# Sheet1.net
KiCad netlist of a schematic drawn in Altium Designer
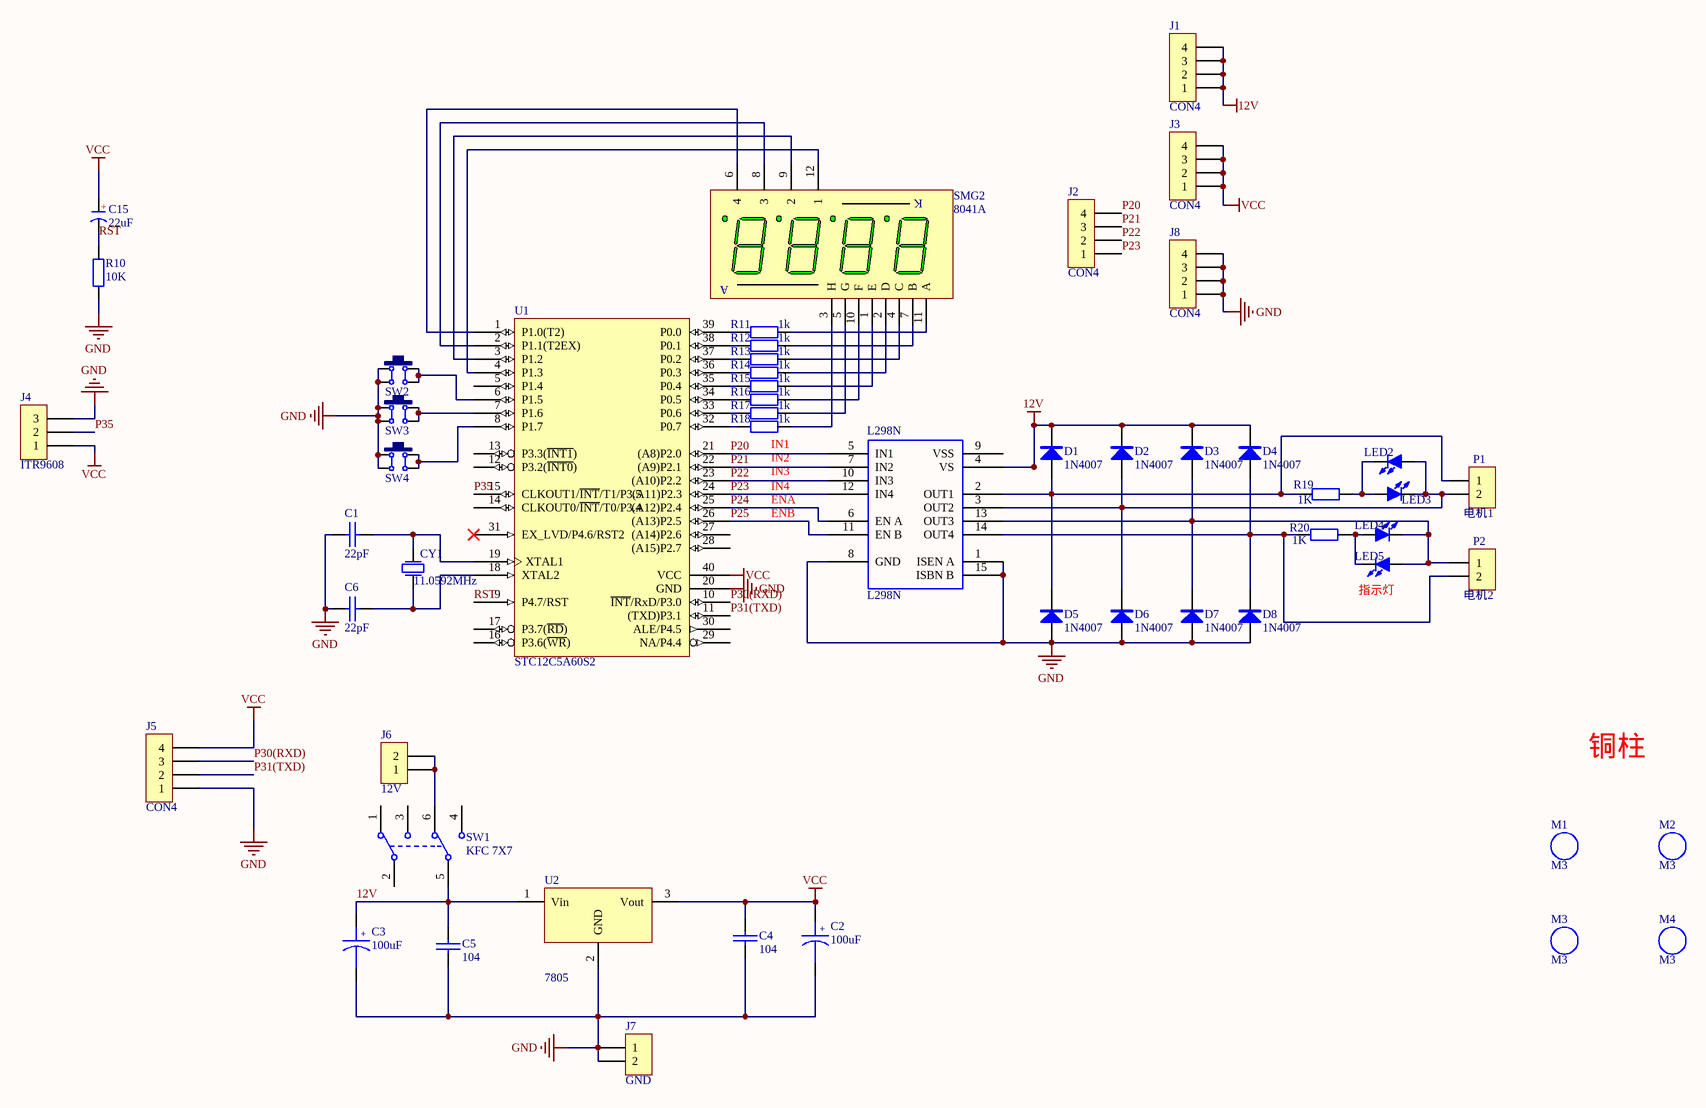
[diagram p0: Sheet1.SchDoc]

(export (version "E")
  (design (tool "Eeschema 10.0.6"))
  (components
    (comp (ref "C1") (value "22pF") (footprint "瓷片电容") (libsource (lib "C电容") (part "CAP1")))
    (comp (ref "C2")
      (value "100uF")
      (footprint "CAP 2.5*5*11")
      (description "Capacitor")
      (libsource (lib "电容") (part "电解电容"))
    )
    (comp (ref "C3")
      (value "100uF")
      (footprint "CAP 2.5*5*11")
      (description "Capacitor")
      (libsource (lib "电容") (part "电解电容"))
    )
    (comp (ref "C4")
      (value "104")
      (footprint "C 0805_M")
      (description "Capacitor")
      (libsource (lib "电容") (part "普通电容"))
    )
    (comp (ref "C5")
      (value "104")
      (footprint "C 0805_M")
      (description "Capacitor")
      (libsource (lib "电容") (part "普通电容"))
    )
    (comp (ref "C6") (value "22pF") (footprint "瓷片电容") (libsource (lib "C电容") (part "CAP1")))
    (comp (ref "C15")
      (value "22uF")
      (footprint "CAP 2.5*5*11")
      (description "直插固态电容")
      (fields (field (name "版权归属") "源创客"))
      (libsource (lib "3.1   - 电阻-电容-电感") (part "C-CS"))
    )
    (comp (ref "CY1") (value "11.0592MHz") (footprint "XTAL-1") (libsource (lib "CRY晶振") (part "CRY")))
    (comp (ref "D1")
      (value "1N4007")
      (footprint "SOD-123")
      (description "整流二极管")
      (fields (field (name "版权归属") "源创客"))
      (libsource (lib "8.1   - 二极管-整流桥") (part "1N4007"))
    )
    (comp (ref "D2")
      (value "1N4007")
      (footprint "SOD-123")
      (description "整流二极管")
      (fields (field (name "版权归属") "源创客"))
      (libsource (lib "8.1   - 二极管-整流桥") (part "1N4007"))
    )
    (comp (ref "D3")
      (value "1N4007")
      (footprint "SOD-123")
      (description "整流二极管")
      (fields (field (name "版权归属") "源创客"))
      (libsource (lib "8.1   - 二极管-整流桥") (part "1N4007"))
    )
    (comp (ref "D4")
      (value "1N4007")
      (footprint "SOD-123")
      (description "整流二极管")
      (fields (field (name "版权归属") "源创客"))
      (libsource (lib "8.1   - 二极管-整流桥") (part "1N4007"))
    )
    (comp (ref "D5")
      (value "1N4007")
      (footprint "SOD-123")
      (description "整流二极管")
      (fields (field (name "版权归属") "源创客"))
      (libsource (lib "8.1   - 二极管-整流桥") (part "1N4007"))
    )
    (comp (ref "D6")
      (value "1N4007")
      (footprint "SOD-123")
      (description "整流二极管")
      (fields (field (name "版权归属") "源创客"))
      (libsource (lib "8.1   - 二极管-整流桥") (part "1N4007"))
    )
    (comp (ref "D7")
      (value "1N4007")
      (footprint "SOD-123")
      (description "整流二极管")
      (fields (field (name "版权归属") "源创客"))
      (libsource (lib "8.1   - 二极管-整流桥") (part "1N4007"))
    )
    (comp (ref "D8")
      (value "1N4007")
      (footprint "SOD-123")
      (description "整流二极管")
      (fields (field (name "版权归属") "源创客"))
      (libsource (lib "8.1   - 二极管-整流桥") (part "1N4007"))
    )
    (comp (ref "J1") (value "CON4") (footprint "SIP4") (libsource (lib "常用元件库") (part "CON4")))
    (comp (ref "J2")
      (value "CON4")
      (footprint "SIP4")
      (description "Connector")
      (libsource (lib "接口") (part "CON4"))
    )
    (comp (ref "J3") (value "CON4") (footprint "SIP4") (libsource (lib "常用元件库") (part "CON4")))
    (comp (ref "J4") (value "ITR9608") (footprint "SIP3") (libsource (lib "常用元件库") (part "CON3")))
    (comp (ref "J5")
      (value "CON4")
      (footprint "SIP4")
      (description "Connector")
      (libsource (lib "接口") (part "CON4"))
    )
    (comp (ref "J6")
      (value "12V")
      (footprint "SIP2")
      (description "Connector")
      (libsource (lib "") (part "CON2_1"))
    )
    (comp (ref "J7")
      (value "GND")
      (footprint "SIP2")
      (description "Connector")
      (libsource (lib "接口") (part "CON2"))
    )
    (comp (ref "J8") (value "CON4") (footprint "SIP4") (libsource (lib "常用元件库") (part "CON4")))
    (comp (ref "L298N") (value "L298N") (footprint "L298N散热片") (libsource (lib "Schlib1") (part "L298N")))
    (comp (ref "LED2")
      (value "红色")
      (footprint "LED 3MM-B")
      (description "插件LED")
      (fields (field (name "版权归属") "源创客"))
      (libsource (lib "9.1   - LED") (part "LED-3MM"))
    )
    (comp (ref "LED3")
      (value "红色")
      (footprint "LED 3MM-B")
      (description "插件LED")
      (fields (field (name "版权归属") "源创客"))
      (libsource (lib "9.1   - LED") (part "LED-3MM"))
    )
    (comp (ref "LED4")
      (value "红色")
      (footprint "LED 3MM-B")
      (description "插件LED")
      (fields (field (name "版权归属") "源创客"))
      (libsource (lib "9.1   - LED") (part "LED-3MM"))
    )
    (comp (ref "LED5")
      (value "红色")
      (footprint "LED 3MM-B")
      (description "插件LED")
      (fields (field (name "版权归属") "源创客"))
      (libsource (lib "9.1   - LED") (part "LED-3MM"))
    )
    (comp (ref "M1")
      (value "M3")
      (footprint "M3x4+6_L")
      (description "铜柱孔")
      (fields (field (name "版权归属") "源创客"))
      (libsource (lib "15.1 - 未分类器件") (part "M3"))
    )
    (comp (ref "M2")
      (value "M3")
      (footprint "M3x4+6_L")
      (description "铜柱孔")
      (fields (field (name "版权归属") "源创客"))
      (libsource (lib "15.1 - 未分类器件") (part "M3"))
    )
    (comp (ref "M3")
      (value "M3")
      (footprint "M3x4+6_L")
      (description "铜柱孔")
      (fields (field (name "版权归属") "源创客"))
      (libsource (lib "15.1 - 未分类器件") (part "M3"))
    )
    (comp (ref "M4")
      (value "M3")
      (footprint "M3x4+6_L")
      (description "铜柱孔")
      (fields (field (name "版权归属") "源创客"))
      (libsource (lib "15.1 - 未分类器件") (part "M3"))
    )
    (comp (ref "P1")
      (value "电机1")
      (footprint "HDR2.54-LI-2P")
      (description "2P接插件")
      (fields (field (name "版权归属") "源创客"))
      (libsource (lib "4.3   - 接插件-脚距1.27") (part "Header 2"))
    )
    (comp (ref "P2")
      (value "电机2")
      (footprint "HDR2.54-LI-2P")
      (description "2P接插件")
      (fields (field (name "版权归属") "源创客"))
      (libsource (lib "4.3   - 接插件-脚距1.27") (part "Header 2"))
    )
    (comp (ref "R10")
      (value "10K")
      (footprint "R 0805_M")
      (description "直插色环电阻")
      (fields (field (name "版权归属") "源创客"))
      (libsource (lib "3.1   - 电阻-电容-电感") (part "R-CRR"))
    )
    (comp (ref "R11")
      (value "1k")
      (footprint "RS 1/2W")
      (description "直插色环电阻")
      (fields (field (name "版权归属") "源创客"))
      (libsource (lib "3.1   - 电阻-电容-电感") (part "R-CRR"))
    )
    (comp (ref "R12")
      (value "1k")
      (footprint "RS 1/2W")
      (description "直插色环电阻")
      (fields (field (name "版权归属") "源创客"))
      (libsource (lib "3.1   - 电阻-电容-电感") (part "R-CRR"))
    )
    (comp (ref "R13")
      (value "1k")
      (footprint "RS 1/2W")
      (description "直插色环电阻")
      (fields (field (name "版权归属") "源创客"))
      (libsource (lib "3.1   - 电阻-电容-电感") (part "R-CRR"))
    )
    (comp (ref "R14")
      (value "1k")
      (footprint "RS 1/2W")
      (description "直插色环电阻")
      (fields (field (name "版权归属") "源创客"))
      (libsource (lib "3.1   - 电阻-电容-电感") (part "R-CRR"))
    )
    (comp (ref "R15")
      (value "1k")
      (footprint "RS 1/2W")
      (description "直插色环电阻")
      (fields (field (name "版权归属") "源创客"))
      (libsource (lib "3.1   - 电阻-电容-电感") (part "R-CRR"))
    )
    (comp (ref "R16")
      (value "1k")
      (footprint "RS 1/2W")
      (description "直插色环电阻")
      (fields (field (name "版权归属") "源创客"))
      (libsource (lib "3.1   - 电阻-电容-电感") (part "R-CRR"))
    )
    (comp (ref "R17")
      (value "1k")
      (footprint "RS 1/2W")
      (description "直插色环电阻")
      (fields (field (name "版权归属") "源创客"))
      (libsource (lib "3.1   - 电阻-电容-电感") (part "R-CRR"))
    )
    (comp (ref "R18")
      (value "1k")
      (footprint "RS 1/2W")
      (description "直插色环电阻")
      (fields (field (name "版权归属") "源创客"))
      (libsource (lib "3.1   - 电阻-电容-电感") (part "R-CRR"))
    )
    (comp (ref "R19")
      (value "1K")
      (footprint "R 0805_M")
      (description "直插色环电阻")
      (fields (field (name "版权归属") "源创客"))
      (libsource (lib "3.1   - 电阻-电容-电感") (part "R-CRR"))
    )
    (comp (ref "R20")
      (value "1K")
      (footprint "R 0805_M")
      (description "直插色环电阻")
      (fields (field (name "版权归属") "源创客"))
      (libsource (lib "3.1   - 电阻-电容-电感") (part "R-CRR"))
    )
    (comp (ref "SMG2")
      (value "8041A")
      (footprint "SMG 0.39-4P_A")
      (description "0.8寸4位共阴数码管")
      (fields (field (name "版权归属") "源创客"))
      (libsource (lib "9.3   - 数码管") (part "8041A"))
    )
    (comp (ref "SW1")
      (value "KFC 7X7")
      (footprint "KFC DIP-7X7")
      (description "7*7自锁开关")
      (fields (field (name "版权归属") "源创客"))
      (libsource (lib "5.1   - 按键-开关") (part "KFC 7X7"))
    )
    (comp (ref "SW2")
      (value "6x6x5")
      (footprint "TSW DIP-6*6*6")
      (description "直插6x6轻触开关")
      (fields (field (name "版权归属") "源创客"))
      (libsource (lib "5.1   - 按键-开关") (part "TSW DIP-6x6"))
    )
    (comp (ref "SW3")
      (value "6x6x5")
      (footprint "TSW DIP-6*6*6")
      (description "直插6x6轻触开关")
      (fields (field (name "版权归属") "源创客"))
      (libsource (lib "5.1   - 按键-开关") (part "TSW DIP-6x6"))
    )
    (comp (ref "SW4")
      (value "6x6x5")
      (footprint "TSW DIP-6*6*6")
      (description "直插6x6轻触开关")
      (fields (field (name "版权归属") "源创客"))
      (libsource (lib "5.1   - 按键-开关") (part "TSW DIP-6x6"))
    )
    (comp (ref "U1")
      (value "STC12C5A60S2")
      (footprint "DIP40-600")
      (description "8-Bit Microcontroller with 32K Flash ROM")
      (libsource (lib "单片机8051") (part "AT89C51RC"))
    )
    (comp (ref "U2") (value "7805") (footprint "TO126") (libsource (lib "Schlib2") (part "7805")))
  )
  (nets
    (net (code "1") (name "/P20") (class "Default")
      (node (ref "J2") (pin "4") (pinfunction "4_4") (pintype "passive"))
      (node (ref "L298N") (pin "5") (pinfunction "IN1_5") (pintype "passive"))
      (node (ref "U1") (pin "21") (pinfunction "(A8)P2.0_21") (pintype "bidirectional"))
    )
    (net (code "2") (name "/P21") (class "Default")
      (node (ref "J2") (pin "3") (pinfunction "3_3") (pintype "passive"))
      (node (ref "L298N") (pin "7") (pinfunction "IN2_7") (pintype "passive"))
      (node (ref "U1") (pin "22") (pinfunction "(A9)P2.1_22") (pintype "bidirectional"))
    )
    (net (code "3") (name "/P22") (class "Default")
      (node (ref "J2") (pin "2") (pinfunction "2_2") (pintype "passive"))
      (node (ref "L298N") (pin "10") (pinfunction "IN3_10") (pintype "passive"))
      (node (ref "U1") (pin "23") (pinfunction "(A10)P2.2_23") (pintype "bidirectional"))
    )
    (net (code "4") (name "/P23") (class "Default")
      (node (ref "J2") (pin "1") (pinfunction "1_1") (pintype "passive"))
      (node (ref "L298N") (pin "12") (pinfunction "IN4_12") (pintype "passive"))
      (node (ref "U1") (pin "24") (pinfunction "(A11)P2.3_24") (pintype "bidirectional"))
    )
    (net (code "5") (name "/P24") (class "Default")
      (node (ref "L298N") (pin "6") (pinfunction "EN_A_6") (pintype "passive"))
      (node (ref "U1") (pin "25") (pinfunction "(A12)P2.4_25") (pintype "bidirectional"))
    )
    (net (code "6") (name "/P25") (class "Default")
      (node (ref "L298N") (pin "11") (pinfunction "EN_B_11") (pintype "passive"))
      (node (ref "U1") (pin "26") (pinfunction "(A13)P2.5_26") (pintype "bidirectional"))
    )
    (net (code "7") (name "/P30(RXD)") (class "Default")
      (node (ref "J5") (pin "3") (pinfunction "3_3") (pintype "passive"))
      (node (ref "U1") (pin "10") (pinfunction "~{INT}/RxD/P3.0_10") (pintype "bidirectional"))
    )
    (net (code "8") (name "/P31(TXD)") (class "Default")
      (node (ref "J5") (pin "2") (pinfunction "2_2") (pintype "passive"))
      (node (ref "U1") (pin "11") (pinfunction "(TXD)P3.1_11") (pintype "bidirectional"))
    )
    (net (code "9") (name "/P35") (class "Default")
      (node (ref "J4") (pin "2") (pinfunction "2_2") (pintype "passive"))
      (node (ref "U1") (pin "15") (pinfunction "CLKOUT1/~{INT}/T1/P3.5_15") (pintype "bidirectional"))
    )
    (net (code "10") (name "/RST") (class "Default")
      (node (ref "C15") (pin "2") (pinfunction "K_2") (pintype "passive"))
      (node (ref "R10") (pin "1") (pinfunction "1_1") (pintype "passive"))
      (node (ref "U1") (pin "9") (pinfunction "P4.7/RST_9") (pintype "input"))
    )
    (net (code "11") (name "12V") (class "Default")
      (node (ref "C3") (pin "1") (pinfunction "1_1") (pintype "passive"))
      (node (ref "C5") (pin "1") (pinfunction "1_1") (pintype "passive"))
      (node (ref "D1") (pin "2") (pinfunction "K_2") (pintype "passive"))
      (node (ref "D2") (pin "2") (pinfunction "K_2") (pintype "passive"))
      (node (ref "D3") (pin "2") (pinfunction "K_2") (pintype "passive"))
      (node (ref "D4") (pin "2") (pinfunction "K_2") (pintype "passive"))
      (node (ref "J1") (pin "1") (pinfunction "1_1") (pintype "passive"))
      (node (ref "J1") (pin "2") (pinfunction "2_2") (pintype "passive"))
      (node (ref "J1") (pin "3") (pinfunction "3_3") (pintype "passive"))
      (node (ref "J1") (pin "4") (pinfunction "4_4") (pintype "passive"))
      (node (ref "L298N") (pin "4") (pinfunction "VS_4") (pintype "passive"))
      (node (ref "SW1") (pin "5") (pinfunction "COM2_5") (pintype "passive"))
      (node (ref "U2") (pin "1") (pinfunction "Vin_1") (pintype "passive"))
    )
    (net (code "12") (name "GND") (class "Default")
      (node (ref "C1") (pin "1") (pinfunction "1_1") (pintype "passive"))
      (node (ref "C2") (pin "2") (pinfunction "2_2") (pintype "passive"))
      (node (ref "C3") (pin "2") (pinfunction "2_2") (pintype "passive"))
      (node (ref "C4") (pin "2") (pinfunction "2_2") (pintype "passive"))
      (node (ref "C5") (pin "2") (pinfunction "2_2") (pintype "passive"))
      (node (ref "C6") (pin "1") (pinfunction "1_1") (pintype "passive"))
      (node (ref "D5") (pin "1") (pinfunction "A_1") (pintype "passive"))
      (node (ref "D6") (pin "1") (pinfunction "A_1") (pintype "passive"))
      (node (ref "D7") (pin "1") (pinfunction "A_1") (pintype "passive"))
      (node (ref "D8") (pin "1") (pinfunction "A_1") (pintype "passive"))
      (node (ref "J4") (pin "3") (pinfunction "3_3") (pintype "passive"))
      (node (ref "J5") (pin "1") (pinfunction "1_1") (pintype "passive"))
      (node (ref "J7") (pin "1") (pinfunction "1_1") (pintype "passive"))
      (node (ref "J7") (pin "2") (pinfunction "2_2") (pintype "passive"))
      (node (ref "J8") (pin "1") (pinfunction "1_1") (pintype "passive"))
      (node (ref "J8") (pin "2") (pinfunction "2_2") (pintype "passive"))
      (node (ref "J8") (pin "3") (pinfunction "3_3") (pintype "passive"))
      (node (ref "J8") (pin "4") (pinfunction "4_4") (pintype "passive"))
      (node (ref "L298N") (pin "1") (pinfunction "ISEN_A_1") (pintype "passive"))
      (node (ref "L298N") (pin "15") (pinfunction "ISBN_B_15") (pintype "passive"))
      (node (ref "L298N") (pin "8") (pinfunction "GND_8") (pintype "passive"))
      (node (ref "R10") (pin "2") (pinfunction "2_2") (pintype "passive"))
      (node (ref "SW2") (pin "1") (pinfunction "1_1") (pintype "passive"))
      (node (ref "SW2") (pin "4") (pinfunction "4_4") (pintype "passive"))
      (node (ref "SW3") (pin "1") (pinfunction "1_1") (pintype "passive"))
      (node (ref "SW3") (pin "4") (pinfunction "4_4") (pintype "passive"))
      (node (ref "SW4") (pin "1") (pinfunction "1_1") (pintype "passive"))
      (node (ref "SW4") (pin "4") (pinfunction "4_4") (pintype "passive"))
      (node (ref "U1") (pin "20") (pinfunction "GND_20") (pintype "power_in"))
      (node (ref "U2") (pin "2") (pinfunction "GND_2") (pintype "passive"))
    )
    (net (code "13") (name "Net-(CY1-P1)") (class "Default")
      (node (ref "C1") (pin "2") (pinfunction "2_2") (pintype "passive"))
      (node (ref "CY1") (pin "1") (pinfunction "P1_1") (pintype "passive"))
      (node (ref "U1") (pin "19") (pinfunction "XTAL1_19") (pintype "input"))
    )
    (net (code "14") (name "Net-(CY1-P2)") (class "Default")
      (node (ref "C6") (pin "2") (pinfunction "2_2") (pintype "passive"))
      (node (ref "CY1") (pin "2") (pinfunction "P2_2") (pintype "passive"))
      (node (ref "U1") (pin "18") (pinfunction "XTAL2_18") (pintype "input"))
    )
    (net (code "15") (name "Net-(D1-A)") (class "Default")
      (node (ref "D1") (pin "1") (pinfunction "A_1") (pintype "passive"))
      (node (ref "D5") (pin "2") (pinfunction "K_2") (pintype "passive"))
      (node (ref "L298N") (pin "2") (pinfunction "OUT1_2") (pintype "passive"))
      (node (ref "P1") (pin "1") (pinfunction "1_1") (pintype "passive"))
      (node (ref "R19") (pin "2") (pinfunction "2_2") (pintype "passive"))
    )
    (net (code "16") (name "Net-(D2-A)") (class "Default")
      (node (ref "D2") (pin "1") (pinfunction "A_1") (pintype "passive"))
      (node (ref "D6") (pin "2") (pinfunction "K_2") (pintype "passive"))
      (node (ref "L298N") (pin "3") (pinfunction "OUT2_3") (pintype "passive"))
      (node (ref "LED2") (pin "1") (pinfunction "A_1") (pintype "passive"))
      (node (ref "LED3") (pin "2") (pinfunction "K_2") (pintype "passive"))
      (node (ref "P1") (pin "2") (pinfunction "2_2") (pintype "passive"))
    )
    (net (code "17") (name "Net-(D3-A)") (class "Default")
      (node (ref "D3") (pin "1") (pinfunction "A_1") (pintype "passive"))
      (node (ref "D7") (pin "2") (pinfunction "K_2") (pintype "passive"))
      (node (ref "L298N") (pin "13") (pinfunction "OUT3_13") (pintype "passive"))
      (node (ref "LED4") (pin "2") (pinfunction "K_2") (pintype "passive"))
      (node (ref "LED5") (pin "1") (pinfunction "A_1") (pintype "passive"))
      (node (ref "P2") (pin "1") (pinfunction "1_1") (pintype "passive"))
    )
    (net (code "18") (name "Net-(D4-A)") (class "Default")
      (node (ref "D4") (pin "1") (pinfunction "A_1") (pintype "passive"))
      (node (ref "D8") (pin "2") (pinfunction "K_2") (pintype "passive"))
      (node (ref "L298N") (pin "14") (pinfunction "OUT4_14") (pintype "passive"))
      (node (ref "P2") (pin "2") (pinfunction "2_2") (pintype "passive"))
      (node (ref "R20") (pin "2") (pinfunction "2_2") (pintype "passive"))
    )
    (net (code "19") (name "Net-(LED2-K)") (class "Default")
      (node (ref "LED2") (pin "2") (pinfunction "K_2") (pintype "passive"))
      (node (ref "LED3") (pin "1") (pinfunction "A_1") (pintype "passive"))
      (node (ref "R19") (pin "1") (pinfunction "1_1") (pintype "passive"))
    )
    (net (code "20") (name "Net-(LED4-A)") (class "Default")
      (node (ref "LED4") (pin "1") (pinfunction "A_1") (pintype "passive"))
      (node (ref "LED5") (pin "2") (pinfunction "K_2") (pintype "passive"))
      (node (ref "R20") (pin "1") (pinfunction "1_1") (pintype "passive"))
    )
    (net (code "21") (name "Net-(SMG2-1)") (class "Default")
      (node (ref "SMG2") (pin "12") (pinfunction "1_12") (pintype "passive"))
      (node (ref "U1") (pin "4") (pinfunction "P1.3_4") (pintype "bidirectional"))
    )
    (net (code "22") (name "Net-(SMG2-2)") (class "Default")
      (node (ref "SMG2") (pin "9") (pinfunction "2_9") (pintype "passive"))
      (node (ref "U1") (pin "3") (pinfunction "P1.2_3") (pintype "bidirectional"))
    )
    (net (code "23") (name "Net-(SMG2-3)") (class "Default")
      (node (ref "SMG2") (pin "8") (pinfunction "3_8") (pintype "passive"))
      (node (ref "U1") (pin "2") (pinfunction "P1.1(T2EX)_2") (pintype "bidirectional"))
    )
    (net (code "24") (name "Net-(SMG2-4)") (class "Default")
      (node (ref "SMG2") (pin "6") (pinfunction "4_6") (pintype "passive"))
      (node (ref "U1") (pin "1") (pinfunction "P1.0(T2)_1") (pintype "bidirectional"))
    )
    (net (code "25") (name "Net-(SMG2-A)") (class "Default")
      (node (ref "R11") (pin "1") (pinfunction "1_1") (pintype "passive"))
      (node (ref "SMG2") (pin "11") (pinfunction "A_11") (pintype "passive"))
    )
    (net (code "26") (name "Net-(SMG2-B)") (class "Default")
      (node (ref "R12") (pin "1") (pinfunction "1_1") (pintype "passive"))
      (node (ref "SMG2") (pin "7") (pinfunction "B_7") (pintype "passive"))
    )
    (net (code "27") (name "Net-(SMG2-C)") (class "Default")
      (node (ref "R13") (pin "1") (pinfunction "1_1") (pintype "passive"))
      (node (ref "SMG2") (pin "4") (pinfunction "C_4") (pintype "passive"))
    )
    (net (code "28") (name "Net-(SMG2-D)") (class "Default")
      (node (ref "R14") (pin "1") (pinfunction "1_1") (pintype "passive"))
      (node (ref "SMG2") (pin "2") (pinfunction "D_2") (pintype "passive"))
    )
    (net (code "29") (name "Net-(SMG2-E)") (class "Default")
      (node (ref "R15") (pin "1") (pinfunction "1_1") (pintype "passive"))
      (node (ref "SMG2") (pin "1") (pinfunction "E_1") (pintype "passive"))
    )
    (net (code "30") (name "Net-(SMG2-F)") (class "Default")
      (node (ref "R16") (pin "1") (pinfunction "1_1") (pintype "passive"))
      (node (ref "SMG2") (pin "10") (pinfunction "F_10") (pintype "passive"))
    )
    (net (code "31") (name "Net-(SMG2-G)") (class "Default")
      (node (ref "R17") (pin "1") (pinfunction "1_1") (pintype "passive"))
      (node (ref "SMG2") (pin "5") (pinfunction "G_5") (pintype "passive"))
    )
    (net (code "32") (name "Net-(SMG2-H)") (class "Default")
      (node (ref "R18") (pin "1") (pinfunction "1_1") (pintype "passive"))
      (node (ref "SMG2") (pin "3") (pinfunction "H_3") (pintype "passive"))
    )
    (net (code "33") (name "Net-(SW1-NC2)") (class "Default")
      (node (ref "J6") (pin "1") (pinfunction "1_1") (pintype "passive"))
      (node (ref "J6") (pin "2") (pinfunction "2_2") (pintype "passive"))
      (node (ref "SW1") (pin "6") (pinfunction "NC2_6") (pintype "passive"))
    )
    (net (code "34") (name "Net-(U1-P0.0)") (class "Default")
      (node (ref "R11") (pin "2") (pinfunction "2_2") (pintype "passive"))
      (node (ref "U1") (pin "39") (pinfunction "P0.0_39") (pintype "bidirectional"))
    )
    (net (code "35") (name "Net-(U1-P0.1)") (class "Default")
      (node (ref "R12") (pin "2") (pinfunction "2_2") (pintype "passive"))
      (node (ref "U1") (pin "38") (pinfunction "P0.1_38") (pintype "bidirectional"))
    )
    (net (code "36") (name "Net-(U1-P0.2)") (class "Default")
      (node (ref "R13") (pin "2") (pinfunction "2_2") (pintype "passive"))
      (node (ref "U1") (pin "37") (pinfunction "P0.2_37") (pintype "bidirectional"))
    )
    (net (code "37") (name "Net-(U1-P0.3)") (class "Default")
      (node (ref "R14") (pin "2") (pinfunction "2_2") (pintype "passive"))
      (node (ref "U1") (pin "36") (pinfunction "P0.3_36") (pintype "bidirectional"))
    )
    (net (code "38") (name "Net-(U1-P0.4)") (class "Default")
      (node (ref "R15") (pin "2") (pinfunction "2_2") (pintype "passive"))
      (node (ref "U1") (pin "35") (pinfunction "P0.4_35") (pintype "bidirectional"))
    )
    (net (code "39") (name "Net-(U1-P0.5)") (class "Default")
      (node (ref "R16") (pin "2") (pinfunction "2_2") (pintype "passive"))
      (node (ref "U1") (pin "34") (pinfunction "P0.5_34") (pintype "bidirectional"))
    )
    (net (code "40") (name "Net-(U1-P0.6)") (class "Default")
      (node (ref "R17") (pin "2") (pinfunction "2_2") (pintype "passive"))
      (node (ref "U1") (pin "33") (pinfunction "P0.6_33") (pintype "bidirectional"))
    )
    (net (code "41") (name "Net-(U1-P0.7)") (class "Default")
      (node (ref "R18") (pin "2") (pinfunction "2_2") (pintype "passive"))
      (node (ref "U1") (pin "32") (pinfunction "P0.7_32") (pintype "bidirectional"))
    )
    (net (code "42") (name "Net-(U1-P1.5)") (class "Default")
      (node (ref "SW2") (pin "2") (pinfunction "2_2") (pintype "passive"))
      (node (ref "SW2") (pin "3") (pinfunction "3_3") (pintype "passive"))
      (node (ref "U1") (pin "6") (pinfunction "P1.5_6") (pintype "bidirectional"))
    )
    (net (code "43") (name "Net-(U1-P1.6)") (class "Default")
      (node (ref "SW3") (pin "2") (pinfunction "2_2") (pintype "passive"))
      (node (ref "SW3") (pin "3") (pinfunction "3_3") (pintype "passive"))
      (node (ref "U1") (pin "7") (pinfunction "P1.6_7") (pintype "bidirectional"))
    )
    (net (code "44") (name "Net-(U1-P1.7)") (class "Default")
      (node (ref "SW4") (pin "2") (pinfunction "2_2") (pintype "passive"))
      (node (ref "SW4") (pin "3") (pinfunction "3_3") (pintype "passive"))
      (node (ref "U1") (pin "8") (pinfunction "P1.7_8") (pintype "bidirectional"))
    )
    (net (code "45") (name "VCC") (class "Default")
      (node (ref "C15") (pin "1") (pinfunction "A_1") (pintype "passive"))
      (node (ref "C2") (pin "1") (pinfunction "1_1") (pintype "passive"))
      (node (ref "C4") (pin "1") (pinfunction "1_1") (pintype "passive"))
      (node (ref "J3") (pin "1") (pinfunction "1_1") (pintype "passive"))
      (node (ref "J3") (pin "2") (pinfunction "2_2") (pintype "passive"))
      (node (ref "J3") (pin "3") (pinfunction "3_3") (pintype "passive"))
      (node (ref "J3") (pin "4") (pinfunction "4_4") (pintype "passive"))
      (node (ref "J4") (pin "1") (pinfunction "1_1") (pintype "passive"))
      (node (ref "J5") (pin "4") (pinfunction "4_4") (pintype "passive"))
      (node (ref "U1") (pin "40") (pinfunction "VCC_40") (pintype "power_in"))
      (node (ref "U2") (pin "3") (pinfunction "Vout_3") (pintype "passive"))
    )
    (net (code "46") (name "unconnected-(L298N-VSS-Pad9)") (class "Default")
      (node (ref "L298N") (pin "9") (pinfunction "VSS_9") (pintype "passive"))
    )
    (net (code "47") (name "unconnected-(SW1-COM2-Pad2)") (class "Default")
      (node (ref "SW1") (pin "2") (pinfunction "COM2_2") (pintype "passive"))
    )
    (net (code "48") (name "unconnected-(SW1-NC1-Pad1)") (class "Default")
      (node (ref "SW1") (pin "1") (pinfunction "NC1_1") (pintype "passive"))
    )
    (net (code "49") (name "unconnected-(SW1-NO1-Pad3)") (class "Default")
      (node (ref "SW1") (pin "3") (pinfunction "NO1_3") (pintype "passive"))
    )
    (net (code "50") (name "unconnected-(SW1-NO2-Pad4)") (class "Default")
      (node (ref "SW1") (pin "4") (pinfunction "NO2_4") (pintype "passive"))
    )
    (net (code "51") (name "unconnected-(U1-(A14)P2.6-Pad27)") (class "Default")
      (node (ref "U1") (pin "27") (pinfunction "(A14)P2.6_27") (pintype "bidirectional"))
    )
    (net (code "52") (name "unconnected-(U1-(A15)P2.7-Pad28)") (class "Default")
      (node (ref "U1") (pin "28") (pinfunction "(A15)P2.7_28") (pintype "bidirectional"))
    )
    (net (code "53") (name "unconnected-(U1-ALE{slash}P4.5-Pad30)") (class "Default")
      (node (ref "U1") (pin "30") (pinfunction "ALE/P4.5_30") (pintype "output"))
    )
    (net (code "54") (name "unconnected-(U1-CLKOUT0{slash}~{INT}{slash}T0{slash}P3.4-Pad14)") (class "Default")
      (node (ref "U1") (pin "14") (pinfunction "CLKOUT0/~{INT}/T0/P3.4_14") (pintype "bidirectional"))
    )
    (net (code "55") (name "unconnected-(U1-EX_LVD{slash}P4.6{slash}RST2-Pad31)") (class "Default")
      (node (ref "U1") (pin "31") (pinfunction "EX_LVD/P4.6/RST2_31") (pintype "input+no_connect"))
    )
    (net (code "56") (name "unconnected-(U1-NA{slash}P4.4-Pad29)") (class "Default")
      (node (ref "U1") (pin "29") (pinfunction "NA/P4.4_29") (pintype "output"))
    )
    (net (code "57") (name "unconnected-(U1-P1.4-Pad5)") (class "Default")
      (node (ref "U1") (pin "5") (pinfunction "P1.4_5") (pintype "bidirectional"))
    )
    (net (code "58") (name "unconnected-(U1-P3.2(~{INT0})-Pad12)") (class "Default")
      (node (ref "U1") (pin "12") (pinfunction "P3.2(~{INT0})_12") (pintype "bidirectional"))
    )
    (net (code "59") (name "unconnected-(U1-P3.3(~{INT1})-Pad13)") (class "Default")
      (node (ref "U1") (pin "13") (pinfunction "P3.3(~{INT1})_13") (pintype "bidirectional"))
    )
    (net (code "60") (name "unconnected-(U1-P3.6(~{WR})-Pad16)") (class "Default")
      (node (ref "U1") (pin "16") (pinfunction "P3.6(~{WR})_16") (pintype "bidirectional"))
    )
    (net (code "61") (name "unconnected-(U1-P3.7(~{RD})-Pad17)") (class "Default")
      (node (ref "U1") (pin "17") (pinfunction "P3.7(~{RD})_17") (pintype "bidirectional"))
    )
  )
)
